# LDR.net
KiCad netlist of a schematic drawn in EAGLE
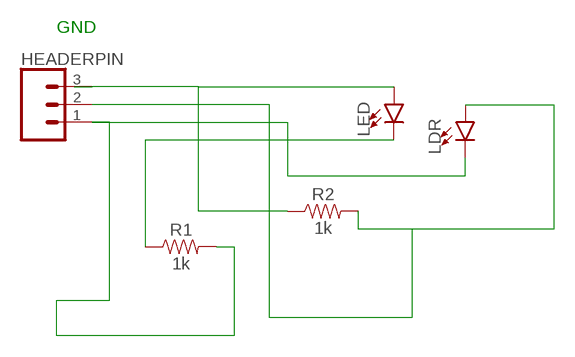
[diagram p0: schematic, sheet 1]

(export (version "E")
  (design (tool "Eeschema 10.0.6"))
  (components
    (comp (ref "HEADERPIN")
      (value "CONN_03")
      (footprint "eagle-import:1X03")
      (libsource (lib "eagle-import") (part "CONN_03"))
    )
    (comp (ref "LDR")
      (value "LED5MM")
      (footprint "eagle-import:LED_5MM")
      (libsource (lib "eagle-import") (part "LED5MM"))
    )
    (comp (ref "LED")
      (value "LED5MM")
      (footprint "eagle-import:LED_5MM")
      (libsource (lib "eagle-import") (part "LED5MM"))
    )
    (comp (ref "R1")
      (value "1k")
      (footprint "eagle-import:AXIAL-0.3")
      (libsource (lib "eagle-import") (part "1KOHM-HORIZ-1/4W-5%"))
    )
    (comp (ref "R2")
      (value "1k")
      (footprint "eagle-import:AXIAL-0.3")
      (libsource (lib "eagle-import") (part "1KOHM-HORIZ-1/4W-5%"))
    )
  )
  (nets
    (net (code "1") (name "Net-(LDR-C)") (class "Default")
      (node (ref "HEADERPIN") (pin "1") (pinfunction "1_1") (pintype "passive"))
      (node (ref "LDR") (pin "K") (pinfunction "C_K") (pintype "passive"))
      (node (ref "R1") (pin "P$2") (pinfunction "2_P$2") (pintype "passive"))
    )
    (net (code "2") (name "Net-(LED-C)") (class "Default")
      (node (ref "LED") (pin "K") (pinfunction "C_K") (pintype "passive"))
      (node (ref "R1") (pin "P$1") (pinfunction "1_P$1") (pintype "passive"))
    )
    (net (code "3") (name "Net-(R2-1)") (class "Default")
      (node (ref "HEADERPIN") (pin "3") (pinfunction "3_3") (pintype "passive"))
      (node (ref "LED") (pin "A") (pinfunction "A_A") (pintype "passive"))
      (node (ref "R2") (pin "P$1") (pinfunction "1_P$1") (pintype "passive"))
    )
    (net (code "4") (name "Net-(R2-2)") (class "Default")
      (node (ref "HEADERPIN") (pin "2") (pinfunction "2_2") (pintype "passive"))
      (node (ref "LDR") (pin "A") (pinfunction "A_A") (pintype "passive"))
      (node (ref "R2") (pin "P$2") (pinfunction "2_P$2") (pintype "passive"))
    )
  )
)
